# Periph.net
KiCad netlist of a schematic drawn in Altium Designer
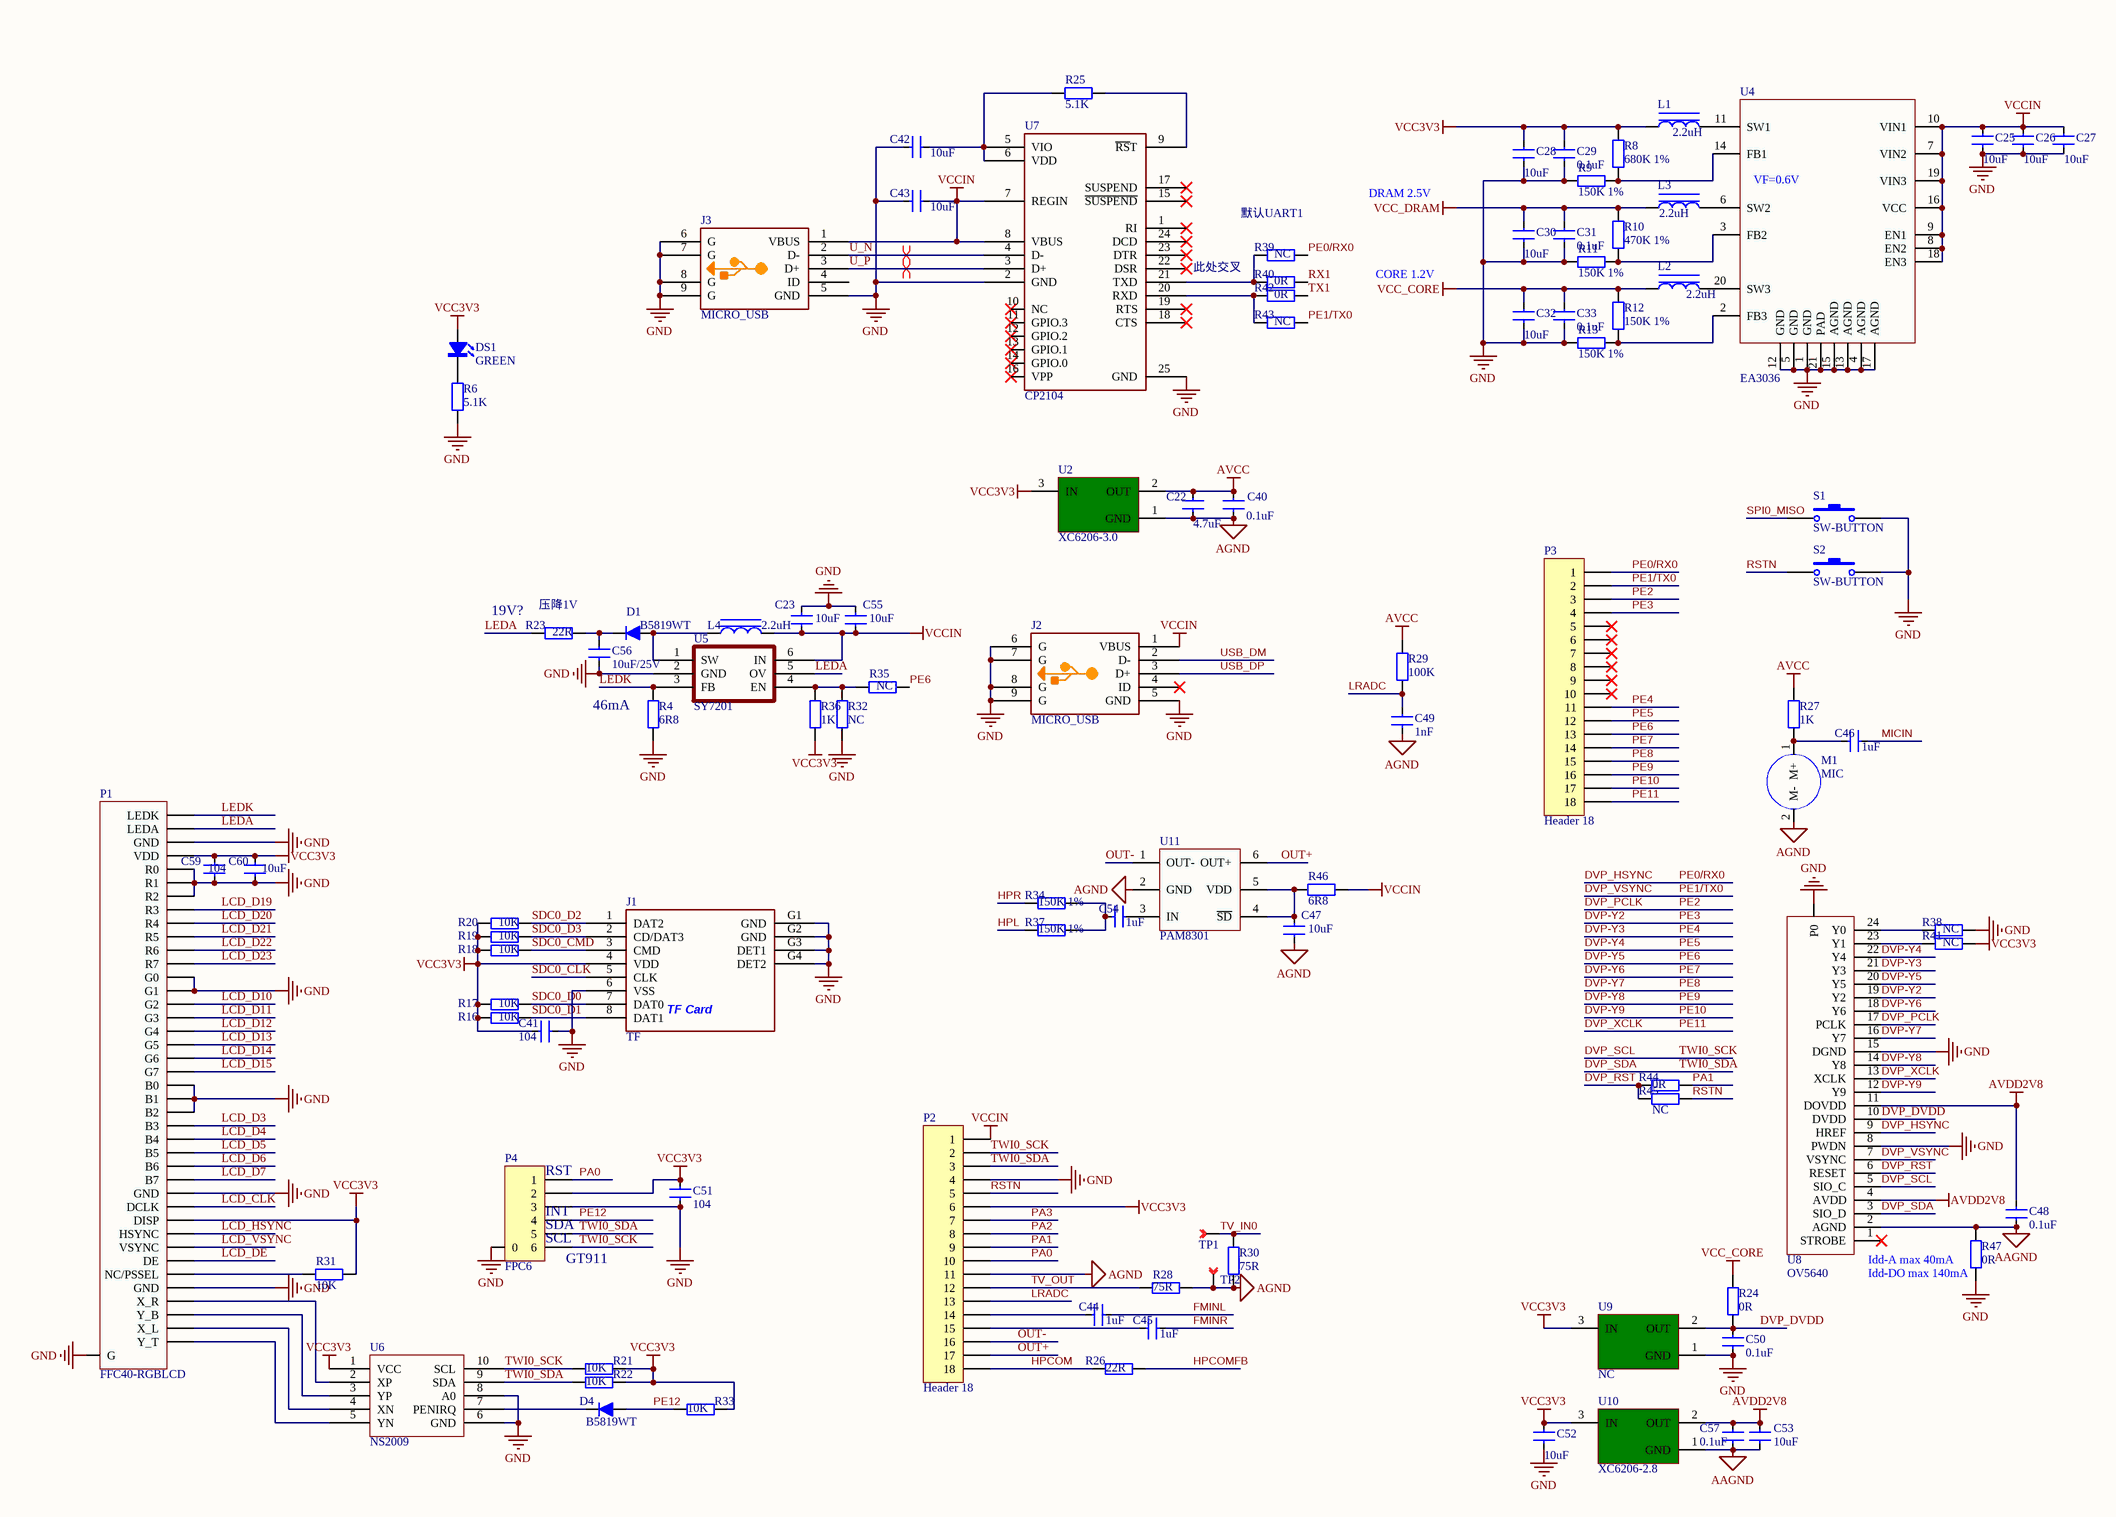
[diagram p0: Periph.SchDoc]

(export (version "E")
  (design (tool "Eeschema 10.0.6"))
  (components
    (comp (ref "C22")
      (value "4.7uF")
      (footprint "C0402")
      (description "普通小电容")
      (libsource (lib "LIB_MANGO") (part "CAP"))
    )
    (comp (ref "C23")
      (value "10uF")
      (footprint "C0402")
      (description "普通小电容")
      (libsource (lib "LIB_MANGO") (part "CAP"))
    )
    (comp (ref "C25")
      (value "10uF")
      (footprint "C0402")
      (description "普通小电容")
      (libsource (lib "LIB_MANGO") (part "CAP"))
    )
    (comp (ref "C26")
      (value "10uF")
      (footprint "C0402")
      (description "普通小电容")
      (libsource (lib "LIB_MANGO") (part "CAP"))
    )
    (comp (ref "C27")
      (value "10uF")
      (footprint "C0402")
      (description "普通小电容")
      (libsource (lib "LIB_MANGO") (part "CAP"))
    )
    (comp (ref "C28")
      (value "10uF")
      (footprint "C0402")
      (description "普通小电容")
      (libsource (lib "LIB_MANGO") (part "CAP"))
    )
    (comp (ref "C29")
      (value "0.1uF")
      (footprint "C0402")
      (description "普通小电容")
      (libsource (lib "LIB_MANGO") (part "CAP"))
    )
    (comp (ref "C30")
      (value "10uF")
      (footprint "C0402")
      (description "普通小电容")
      (libsource (lib "LIB_MANGO") (part "CAP"))
    )
    (comp (ref "C31")
      (value "0.1uF")
      (footprint "C0402")
      (description "普通小电容")
      (libsource (lib "LIB_MANGO") (part "CAP"))
    )
    (comp (ref "C32")
      (value "10uF")
      (footprint "C0402")
      (description "普通小电容")
      (libsource (lib "LIB_MANGO") (part "CAP"))
    )
    (comp (ref "C33")
      (value "0.1uF")
      (footprint "C0402")
      (description "普通小电容")
      (libsource (lib "LIB_MANGO") (part "CAP"))
    )
    (comp (ref "C40")
      (value "0.1uF")
      (footprint "C0402")
      (description "普通小电容")
      (libsource (lib "LIB_MANGO") (part "CAP"))
    )
    (comp (ref "C41")
      (value "104")
      (footprint "C0402")
      (description "普通小电容")
      (libsource (lib "LIB_MANGO") (part "CAP"))
    )
    (comp (ref "C42")
      (value "10uF")
      (footprint "C0402")
      (description "普通小电容")
      (libsource (lib "LIB_MANGO") (part "CAP"))
    )
    (comp (ref "C43")
      (value "10uF")
      (footprint "C0402")
      (description "普通小电容")
      (libsource (lib "LIB_MANGO") (part "CAP"))
    )
    (comp (ref "C44")
      (value "1uF")
      (footprint "C0402")
      (description "普通小电容")
      (libsource (lib "LIB_MANGO") (part "CAP"))
    )
    (comp (ref "C45")
      (value "1uF")
      (footprint "C0402")
      (description "普通小电容")
      (libsource (lib "LIB_MANGO") (part "CAP"))
    )
    (comp (ref "C46")
      (value "1uF")
      (footprint "C0402")
      (description "普通小电容")
      (libsource (lib "LIB_MANGO") (part "CAP"))
    )
    (comp (ref "C47")
      (value "10uF")
      (footprint "C0402")
      (description "普通小电容")
      (libsource (lib "LIB_MANGO") (part "CAP"))
    )
    (comp (ref "C48")
      (value "0.1uF")
      (footprint "C0402")
      (description "普通小电容")
      (libsource (lib "LIB_MANGO") (part "CAP"))
    )
    (comp (ref "C49")
      (value "1nF")
      (footprint "C0402")
      (description "普通小电容")
      (libsource (lib "LIB_MANGO") (part "CAP"))
    )
    (comp (ref "C50")
      (value "0.1uF")
      (footprint "C0402")
      (description "普通小电容")
      (libsource (lib "LIB_MANGO") (part "CAP"))
    )
    (comp (ref "C51")
      (value "104")
      (footprint "C0402")
      (description "普通小电容")
      (libsource (lib "LIB_MANGO") (part "CAP"))
    )
    (comp (ref "C52")
      (value "10uF")
      (footprint "C0402")
      (description "普通小电容")
      (libsource (lib "LIB_MANGO") (part "CAP"))
    )
    (comp (ref "C53")
      (value "10uF")
      (footprint "C0402")
      (description "普通小电容")
      (libsource (lib "LIB_MANGO") (part "CAP"))
    )
    (comp (ref "C54")
      (value "1uF")
      (footprint "C0402")
      (description "普通小电容")
      (libsource (lib "LIB_MANGO") (part "CAP"))
    )
    (comp (ref "C55")
      (value "10uF")
      (footprint "C0402")
      (description "普通小电容")
      (libsource (lib "LIB_MANGO") (part "CAP"))
    )
    (comp (ref "C56")
      (value "10uF/25V")
      (footprint "C0603")
      (description "普通小电容")
      (libsource (lib "LIB_MANGO") (part "CAP"))
    )
    (comp (ref "C57")
      (value "0.1uF")
      (footprint "C0402")
      (description "普通小电容")
      (libsource (lib "LIB_MANGO") (part "CAP"))
    )
    (comp (ref "C59")
      (value "104")
      (footprint "C0402")
      (description "普通小电容")
      (libsource (lib "LIB_MANGO") (part "CAP"))
    )
    (comp (ref "C60")
      (value "10uF")
      (footprint "C0402")
      (description "普通小电容")
      (libsource (lib "LIB_MANGO") (part "CAP"))
    )
    (comp (ref "D1")
      (value "B5819WT")
      (footprint "SOD523")
      (description "普通二极管")
      (libsource (lib "A") (part "Diode"))
    )
    (comp (ref "D4")
      (value "B5819WT")
      (footprint "SOD523")
      (description "普通二极管")
      (libsource (lib "A") (part "Diode"))
    )
    (comp (ref "DS1") (value "GREEN") (footprint "LED0402") (libsource (lib "A") (part "LED")))
    (comp (ref "J1")
      (value "TF")
      (footprint "TFCARD473092651")
      (libsource (lib "LIB_MANGO") (part "TF_473092651"))
    )
    (comp (ref "J2")
      (value "MICRO_USB")
      (footprint "MICROUSB-youxin")
      (libsource (lib "A") (part "MICRO_USB"))
    )
    (comp (ref "J3")
      (value "MICRO_USB")
      (footprint "MICROUSB-youxin")
      (libsource (lib "A") (part "MICRO_USB"))
    )
    (comp (ref "L1")
      (value "2.2uH")
      (footprint "VLS2016")
      (description "普通电感")
      (libsource (lib "LIB_MANGO") (part "L"))
    )
    (comp (ref "L2")
      (value "2.2uH")
      (footprint "VLS2016")
      (description "普通电感")
      (libsource (lib "LIB_MANGO") (part "L"))
    )
    (comp (ref "L3")
      (value "2.2uH")
      (footprint "VLS2016")
      (description "普通电感")
      (libsource (lib "A") (part "L"))
    )
    (comp (ref "L4")
      (value "2.2uH")
      (footprint "VLS3012E")
      (description "普通电感")
      (libsource (lib "LIB_MANGO") (part "L"))
    )
    (comp (ref "M1") (value "MIC") (footprint "MIC") (libsource (lib "LIB_MANGO") (part "MIC")))
    (comp (ref "P1")
      (value "FFC40-RGBLCD")
      (footprint "FFC/SM0.5-1H40")
      (fields (field (name "PUBLISHER") "Altium Limited"))
      (libsource (lib "LIB_MANGO") (part "FFC40-RGBLCD"))
    )
    (comp (ref "P2")
      (value "Header 18")
      (footprint "HDR1X18-M2")
      (description "Header, 18-Pin")
      (fields (field (name "PUBLISHER") "Altium Limited"))
      (libsource (lib "LIB_MANGO") (part "Header 18"))
    )
    (comp (ref "P3")
      (value "Header 18")
      (footprint "HDR1X18-M2")
      (description "Header, 18-Pin")
      (fields (field (name "PUBLISHER") "Altium Limited"))
      (libsource (lib "LIB_MANGO") (part "Header 18"))
    )
    (comp (ref "P4")
      (value "FPC6")
      (footprint "FPC6")
      (fields (field (name "PUBLISHER") "Altium Limited"))
      (libsource (lib "LIB_MANGO") (part "FPC6"))
    )
    (comp (ref "R4")
      (value "6R8")
      (footprint "R0402")
      (description "普通电阻")
      (libsource (lib "LIB_MANGO") (part "RES"))
    )
    (comp (ref "R6")
      (value "5.1K")
      (footprint "R0402")
      (description "普通电阻1%精度")
      (libsource (lib "") (part "RES_2"))
    )
    (comp (ref "R8")
      (value "680K 1%")
      (footprint "R0402")
      (description "普通电阻")
      (libsource (lib "") (part "RES_2"))
    )
    (comp (ref "R9")
      (value "150K 1%")
      (footprint "R0402")
      (description "普通电阻")
      (libsource (lib "") (part "RES_3"))
    )
    (comp (ref "R10")
      (value "470K 1%")
      (footprint "R0402")
      (description "普通电阻")
      (libsource (lib "") (part "RES_2"))
    )
    (comp (ref "R11")
      (value "150K 1%")
      (footprint "R0402")
      (description "普通电阻")
      (libsource (lib "") (part "RES_3"))
    )
    (comp (ref "R12")
      (value "150K 1%")
      (footprint "R0402")
      (description "普通电阻")
      (libsource (lib "") (part "RES_2"))
    )
    (comp (ref "R13")
      (value "150K 1%")
      (footprint "R0402")
      (description "普通电阻")
      (libsource (lib "") (part "RES_3"))
    )
    (comp (ref "R16")
      (value "10K")
      (footprint "R0402")
      (description "普通电阻")
      (libsource (lib "LIB_MANGO") (part "RES"))
    )
    (comp (ref "R17")
      (value "10K")
      (footprint "R0402")
      (description "普通电阻")
      (libsource (lib "LIB_MANGO") (part "RES"))
    )
    (comp (ref "R18")
      (value "10K")
      (footprint "R0402")
      (description "普通电阻")
      (libsource (lib "LIB_MANGO") (part "RES"))
    )
    (comp (ref "R19")
      (value "10K")
      (footprint "R0402")
      (description "普通电阻")
      (libsource (lib "LIB_MANGO") (part "RES"))
    )
    (comp (ref "R20")
      (value "10K")
      (footprint "R0402")
      (description "普通电阻")
      (libsource (lib "LIB_MANGO") (part "RES"))
    )
    (comp (ref "R21")
      (value "10K")
      (footprint "R0402")
      (description "普通电阻")
      (libsource (lib "") (part "RES_1"))
    )
    (comp (ref "R22")
      (value "10K")
      (footprint "R0402")
      (description "普通电阻")
      (libsource (lib "") (part "RES_1"))
    )
    (comp (ref "R23")
      (value "22R")
      (footprint "R0603")
      (description "普通电阻")
      (libsource (lib "") (part "RES_3"))
    )
    (comp (ref "R24")
      (value "0R")
      (footprint "R0402")
      (description "普通电阻")
      (libsource (lib "LIB_MANGO") (part "RES"))
    )
    (comp (ref "R25")
      (value "5.1K")
      (footprint "R0402")
      (description "普通电阻")
      (libsource (lib "") (part "RES_1"))
    )
    (comp (ref "R26")
      (value "22R")
      (footprint "R0402")
      (description "普通电阻")
      (libsource (lib "") (part "RES_1"))
    )
    (comp (ref "R27")
      (value "1K")
      (footprint "R0402")
      (description "普通电阻")
      (libsource (lib "") (part "RES_2"))
    )
    (comp (ref "R28")
      (value "75R")
      (footprint "R0402")
      (description "普通电阻")
      (libsource (lib "") (part "RES_1"))
    )
    (comp (ref "R29")
      (value "100K")
      (footprint "R0402")
      (description "普通电阻")
      (libsource (lib "LIB_MANGO") (part "RES"))
    )
    (comp (ref "R30")
      (value "75R")
      (footprint "R0402")
      (description "普通电阻")
      (libsource (lib "") (part "RES_2"))
    )
    (comp (ref "R31")
      (value "10K")
      (footprint "R0402")
      (description "普通电阻")
      (libsource (lib "") (part "RES_3"))
    )
    (comp (ref "R32")
      (value "NC")
      (footprint "R0402")
      (description "普通电阻")
      (libsource (lib "") (part "RES_2"))
    )
    (comp (ref "R33")
      (value "10K")
      (footprint "R0402")
      (description "普通电阻")
      (libsource (lib "") (part "RES_1"))
    )
    (comp (ref "R34")
      (value "150K 1%")
      (footprint "R0402")
      (description "普通电阻")
      (libsource (lib "") (part "RES_3"))
    )
    (comp (ref "R35")
      (value "NC")
      (footprint "R0402")
      (description "普通电阻")
      (libsource (lib "") (part "RES_1"))
    )
    (comp (ref "R36")
      (value "1K")
      (footprint "R0402")
      (description "普通电阻")
      (libsource (lib "LIB_MANGO") (part "RES"))
    )
    (comp (ref "R37")
      (value "150K 1%")
      (footprint "R0402")
      (description "普通电阻")
      (libsource (lib "") (part "RES_3"))
    )
    (comp (ref "R38")
      (value "NC")
      (footprint "R0402")
      (description "普通电阻")
      (libsource (lib "") (part "RES_1"))
    )
    (comp (ref "R39")
      (value "NC")
      (footprint "R0402")
      (description "普通电阻")
      (libsource (lib "") (part "RES_3"))
    )
    (comp (ref "R40")
      (value "0R")
      (footprint "R0402")
      (description "普通电阻")
      (libsource (lib "") (part "RES_3"))
    )
    (comp (ref "R41")
      (value "NC")
      (footprint "R0402")
      (description "普通电阻")
      (libsource (lib "") (part "RES_1"))
    )
    (comp (ref "R42")
      (value "0R")
      (footprint "R0402")
      (description "普通电阻")
      (libsource (lib "") (part "RES_3"))
    )
    (comp (ref "R43")
      (value "NC")
      (footprint "R0402")
      (description "普通电阻")
      (libsource (lib "") (part "RES_3"))
    )
    (comp (ref "R44")
      (value "0R")
      (footprint "R0402")
      (description "普通电阻")
      (libsource (lib "") (part "RES_3"))
    )
    (comp (ref "R45")
      (value "NC")
      (footprint "R0402")
      (description "普通电阻")
      (libsource (lib "") (part "RES_1"))
    )
    (comp (ref "R46")
      (value "6R8")
      (footprint "R0402")
      (description "普通电阻")
      (libsource (lib "") (part "RES_3"))
    )
    (comp (ref "R47")
      (value "0R")
      (footprint "R0402")
      (description "普通电阻")
      (libsource (lib "") (part "RES_2"))
    )
    (comp (ref "S1")
      (value "SW-BUTTON")
      (footprint "MINIBUTTON")
      (libsource (lib "LIB_MANGO") (part "SW-BUTTON"))
    )
    (comp (ref "S2")
      (value "SW-BUTTON")
      (footprint "MINIBUTTON")
      (libsource (lib "LIB_MANGO") (part "SW-BUTTON"))
    )
    (comp (ref "TP1")
      (value "TEST POINT")
      (footprint "TEST-POINT")
      (description "Description")
      (libsource (lib "LIB_MANGO") (part "TP"))
    )
    (comp (ref "TP2")
      (value "TEST POINT")
      (footprint "TEST-POINT")
      (description "Description")
      (libsource (lib "LIB_MANGO") (part "TP"))
    )
    (comp (ref "U2") (value "XC6206-3.0") (footprint "SOT23") (libsource (lib "LIB_MANGO") (part "XC6206")))
    (comp (ref "U4")
      (value "EA3036")
      (footprint "QFN40P300X300X80_HS-21N")
      (libsource (lib "LIB_MANGO") (part "EA3036"))
    )
    (comp (ref "U5") (value "SY7201") (footprint "SOT23-6") (libsource (lib "LIB_MANGO") (part "PT4101")))
    (comp (ref "U6") (value "NS2009") (footprint "TSSOP10") (libsource (lib "LIB_MANGO") (part "NS2009")))
    (comp (ref "U7") (value "CP2104") (footprint "QFN24") (libsource (lib "LIB_MANGO") (part "CP2104")))
    (comp (ref "U8")
      (value "OV5640")
      (footprint "FFC/SM0.5-1H24 - OV2640")
      (description "Header, 24-Pin")
      (fields (field (name "PUBLISHER") "Altium Limited"))
      (libsource (lib "A") (part "OV5640"))
    )
    (comp (ref "U9") (value "NC") (footprint "SOT23") (libsource (lib "LIB_MANGO") (part "XC6206")))
    (comp (ref "U10") (value "XC6206-2.8") (footprint "SOT23") (libsource (lib "LIB_MANGO") (part "XC6206")))
    (comp (ref "U11") (value "PAM8301") (footprint "SOT23-6") (libsource (lib "LIB_MANGO") (part "PAM8301")))
  )
  (nets
    (net (code "1") (name "/DVP-Y2") (class "Default")
      (node (ref "P3") (pin "4") (pinfunction "4_4") (pintype "passive"))
      (node (ref "U8") (pin "19") (pinfunction "Y2_19") (pintype "passive"))
    )
    (net (code "2") (name "/DVP-Y3") (class "Default")
      (node (ref "P3") (pin "11") (pinfunction "11_11") (pintype "passive"))
      (node (ref "U8") (pin "21") (pinfunction "Y3_21") (pintype "passive"))
    )
    (net (code "3") (name "/DVP-Y4") (class "Default")
      (node (ref "P3") (pin "12") (pinfunction "12_12") (pintype "passive"))
      (node (ref "U8") (pin "22") (pinfunction "Y4_22") (pintype "passive"))
    )
    (net (code "4") (name "/DVP-Y5") (class "Default")
      (node (ref "P3") (pin "13") (pinfunction "13_13") (pintype "passive"))
      (node (ref "R35") (pin "2") (pinfunction "2_2") (pintype "passive"))
      (node (ref "U8") (pin "20") (pinfunction "Y5_20") (pintype "passive"))
    )
    (net (code "5") (name "/DVP-Y6") (class "Default")
      (node (ref "P3") (pin "14") (pinfunction "14_14") (pintype "passive"))
      (node (ref "U8") (pin "18") (pinfunction "Y6_18") (pintype "passive"))
    )
    (net (code "6") (name "/DVP-Y7") (class "Default")
      (node (ref "P3") (pin "15") (pinfunction "15_15") (pintype "passive"))
      (node (ref "U8") (pin "16") (pinfunction "Y7_16") (pintype "passive"))
    )
    (net (code "7") (name "/DVP-Y8") (class "Default")
      (node (ref "P3") (pin "16") (pinfunction "16_16") (pintype "passive"))
      (node (ref "U8") (pin "14") (pinfunction "Y8_14") (pintype "passive"))
    )
    (net (code "8") (name "/DVP-Y9") (class "Default")
      (node (ref "P3") (pin "17") (pinfunction "17_17") (pintype "passive"))
      (node (ref "U8") (pin "12") (pinfunction "Y9_12") (pintype "passive"))
    )
    (net (code "9") (name "/DVP_DVDD") (class "Default")
      (node (ref "C50") (pin "2") (pinfunction "2_2") (pintype "passive"))
      (node (ref "R24") (pin "1") (pinfunction "1_1") (pintype "passive"))
      (node (ref "U8") (pin "10") (pinfunction "DVDD_10") (pintype "passive"))
      (node (ref "U9") (pin "2") (pinfunction "OUT_2") (pintype "passive"))
    )
    (net (code "10") (name "/DVP_HSYNC") (class "Default")
      (node (ref "P3") (pin "1") (pinfunction "1_1") (pintype "passive"))
      (node (ref "R39") (pin "1") (pinfunction "1_1") (pintype "passive"))
      (node (ref "U8") (pin "9") (pinfunction "HREF_9") (pintype "passive"))
    )
    (net (code "11") (name "/DVP_PCLK") (class "Default")
      (node (ref "P3") (pin "3") (pinfunction "3_3") (pintype "passive"))
      (node (ref "U8") (pin "17") (pinfunction "PCLK_17") (pintype "passive"))
    )
    (net (code "12") (name "/DVP_RST") (class "Default")
      (node (ref "R44") (pin "2") (pinfunction "2_2") (pintype "passive"))
      (node (ref "R45") (pin "1") (pinfunction "1_1") (pintype "passive"))
      (node (ref "U8") (pin "6") (pinfunction "RESET_6") (pintype "passive"))
    )
    (net (code "13") (name "/DVP_SCL") (class "Default")
      (node (ref "P2") (pin "2") (pinfunction "2_2") (pintype "passive"))
      (node (ref "P4") (pin "6") (pinfunction "6_6") (pintype "passive"))
      (node (ref "R21") (pin "1") (pinfunction "1_1") (pintype "passive"))
      (node (ref "U6") (pin "10") (pinfunction "SCL_10") (pintype "passive"))
      (node (ref "U8") (pin "5") (pinfunction "SIO_C_5") (pintype "passive"))
    )
    (net (code "14") (name "/DVP_SDA") (class "Default")
      (node (ref "P2") (pin "3") (pinfunction "3_3") (pintype "passive"))
      (node (ref "P4") (pin "5") (pinfunction "5_5") (pintype "passive"))
      (node (ref "R22") (pin "1") (pinfunction "1_1") (pintype "passive"))
      (node (ref "U6") (pin "9") (pinfunction "SDA_9") (pintype "passive"))
      (node (ref "U8") (pin "3") (pinfunction "SIO_D_3") (pintype "passive"))
    )
    (net (code "15") (name "/DVP_VSYNC") (class "Default")
      (node (ref "P3") (pin "2") (pinfunction "2_2") (pintype "passive"))
      (node (ref "R43") (pin "1") (pinfunction "1_1") (pintype "passive"))
      (node (ref "U8") (pin "7") (pinfunction "VSYNC_7") (pintype "passive"))
    )
    (net (code "16") (name "/DVP_XCLK") (class "Default")
      (node (ref "P3") (pin "18") (pinfunction "18_18") (pintype "passive"))
      (node (ref "U8") (pin "13") (pinfunction "XCLK_13") (pintype "passive"))
    )
    (net (code "17") (name "/FMINL") (class "Default")
      (node (ref "C44") (pin "2") (pinfunction "2_2") (pintype "passive"))
    )
    (net (code "18") (name "/FMINR") (class "Default")
      (node (ref "C45") (pin "2") (pinfunction "2_2") (pintype "passive"))
    )
    (net (code "19") (name "/HPCOM") (class "Default")
      (node (ref "P2") (pin "18") (pinfunction "18_18") (pintype "passive"))
      (node (ref "R26") (pin "1") (pinfunction "1_1") (pintype "passive"))
    )
    (net (code "20") (name "/HPCOMFB") (class "Default")
      (node (ref "R26") (pin "2") (pinfunction "2_2") (pintype "passive"))
    )
    (net (code "21") (name "/HPL") (class "Default")
      (node (ref "R37") (pin "2") (pinfunction "2_2") (pintype "passive"))
    )
    (net (code "22") (name "/HPR") (class "Default")
      (node (ref "R34") (pin "2") (pinfunction "2_2") (pintype "passive"))
    )
    (net (code "23") (name "/LCD_CLK") (class "Default")
      (node (ref "P1") (pin "30") (pinfunction "DCLK_30") (pintype "passive"))
    )
    (net (code "24") (name "/LCD_D3") (class "Default")
      (node (ref "P1") (pin "24") (pinfunction "B3_24") (pintype "passive"))
    )
    (net (code "25") (name "/LCD_D4") (class "Default")
      (node (ref "P1") (pin "25") (pinfunction "B4_25") (pintype "passive"))
    )
    (net (code "26") (name "/LCD_D5") (class "Default")
      (node (ref "P1") (pin "26") (pinfunction "B5_26") (pintype "passive"))
    )
    (net (code "27") (name "/LCD_D6") (class "Default")
      (node (ref "P1") (pin "27") (pinfunction "B6_27") (pintype "passive"))
    )
    (net (code "28") (name "/LCD_D7") (class "Default")
      (node (ref "P1") (pin "28") (pinfunction "B7_28") (pintype "passive"))
    )
    (net (code "29") (name "/LCD_D10") (class "Default")
      (node (ref "P1") (pin "15") (pinfunction "G2_15") (pintype "passive"))
    )
    (net (code "30") (name "/LCD_D11") (class "Default")
      (node (ref "P1") (pin "16") (pinfunction "G3_16") (pintype "passive"))
    )
    (net (code "31") (name "/LCD_D12") (class "Default")
      (node (ref "P1") (pin "17") (pinfunction "G4_17") (pintype "passive"))
    )
    (net (code "32") (name "/LCD_D13") (class "Default")
      (node (ref "P1") (pin "18") (pinfunction "G5_18") (pintype "passive"))
    )
    (net (code "33") (name "/LCD_D14") (class "Default")
      (node (ref "P1") (pin "19") (pinfunction "G6_19") (pintype "passive"))
    )
    (net (code "34") (name "/LCD_D15") (class "Default")
      (node (ref "P1") (pin "20") (pinfunction "G7_20") (pintype "passive"))
    )
    (net (code "35") (name "/LCD_D19") (class "Default")
      (node (ref "P1") (pin "8") (pinfunction "R3_8") (pintype "passive"))
    )
    (net (code "36") (name "/LCD_D20") (class "Default")
      (node (ref "P1") (pin "9") (pinfunction "R4_9") (pintype "passive"))
    )
    (net (code "37") (name "/LCD_D21") (class "Default")
      (node (ref "P1") (pin "10") (pinfunction "R5_10") (pintype "passive"))
    )
    (net (code "38") (name "/LCD_D22") (class "Default")
      (node (ref "P1") (pin "11") (pinfunction "R6_11") (pintype "passive"))
    )
    (net (code "39") (name "/LCD_D23") (class "Default")
      (node (ref "P1") (pin "12") (pinfunction "R7_12") (pintype "passive"))
    )
    (net (code "40") (name "/LCD_DE") (class "Default")
      (node (ref "P1") (pin "34") (pinfunction "DE_34") (pintype "passive"))
    )
    (net (code "41") (name "/LCD_HSYNC") (class "Default")
      (node (ref "P1") (pin "32") (pinfunction "HSYNC_32") (pintype "passive"))
    )
    (net (code "42") (name "/LCD_VSYNC") (class "Default")
      (node (ref "P1") (pin "33") (pinfunction "VSYNC_33") (pintype "passive"))
    )
    (net (code "43") (name "/LEDA") (class "Default")
      (node (ref "P1") (pin "2") (pinfunction "LEDA_2") (pintype "passive"))
      (node (ref "R23") (pin "2") (pinfunction "2_2") (pintype "passive"))
      (node (ref "U5") (pin "5") (pinfunction "OV_5") (pintype "passive"))
    )
    (net (code "44") (name "/LEDK") (class "Default")
      (node (ref "P1") (pin "1") (pinfunction "LEDK_1") (pintype "passive"))
      (node (ref "R4") (pin "2") (pinfunction "2_2") (pintype "passive"))
      (node (ref "U5") (pin "3") (pinfunction "FB_3") (pintype "passive"))
    )
    (net (code "45") (name "/LRADC") (class "Default")
      (node (ref "C49") (pin "2") (pinfunction "2_2") (pintype "passive"))
      (node (ref "P2") (pin "13") (pinfunction "13_13") (pintype "passive"))
      (node (ref "R29") (pin "1") (pinfunction "1_1") (pintype "passive"))
    )
    (net (code "46") (name "/MICIN") (class "Default")
      (node (ref "C46") (pin "2") (pinfunction "2_2") (pintype "passive"))
    )
    (net (code "47") (name "/OUT+") (class "Default")
      (node (ref "P2") (pin "17") (pinfunction "17_17") (pintype "passive"))
      (node (ref "U11") (pin "6") (pinfunction "OUT+_6") (pintype "passive"))
    )
    (net (code "48") (name "/OUT-") (class "Default")
      (node (ref "P2") (pin "16") (pinfunction "16_16") (pintype "passive"))
      (node (ref "U11") (pin "1") (pinfunction "OUT-_1") (pintype "passive"))
    )
    (net (code "49") (name "/PA0") (class "Default")
      (node (ref "P2") (pin "10") (pinfunction "10_10") (pintype "passive"))
      (node (ref "P4") (pin "1") (pinfunction "1_1") (pintype "passive"))
    )
    (net (code "50") (name "/PA1") (class "Default")
      (node (ref "P2") (pin "9") (pinfunction "9_9") (pintype "passive"))
      (node (ref "R44") (pin "1") (pinfunction "1_1") (pintype "passive"))
    )
    (net (code "51") (name "/PA2") (class "Default")
      (node (ref "P2") (pin "8") (pinfunction "8_8") (pintype "passive"))
    )
    (net (code "52") (name "/PA3") (class "Default")
      (node (ref "P2") (pin "7") (pinfunction "7_7") (pintype "passive"))
    )
    (net (code "53") (name "/PE12") (class "Default")
      (node (ref "D4") (pin "A") (pinfunction "A_A") (pintype "passive"))
      (node (ref "P4") (pin "4") (pinfunction "4_4") (pintype "passive"))
      (node (ref "R33") (pin "1") (pinfunction "1_1") (pintype "passive"))
    )
    (net (code "54") (name "/RSTN") (class "Default")
      (node (ref "P2") (pin "5") (pinfunction "5_5") (pintype "passive"))
      (node (ref "R45") (pin "2") (pinfunction "2_2") (pintype "passive"))
      (node (ref "S2") (pin "1") (pinfunction "1_1") (pintype "passive"))
    )
    (net (code "55") (name "/RX1") (class "Default")
      (node (ref "R40") (pin "1") (pinfunction "1_1") (pintype "passive"))
    )
    (net (code "56") (name "/SDC0_CLK") (class "Default")
      (node (ref "J1") (pin "5") (pinfunction "CLK_5") (pintype "passive"))
    )
    (net (code "57") (name "/SDC0_CMD") (class "Default")
      (node (ref "J1") (pin "3") (pinfunction "CMD_3") (pintype "passive"))
      (node (ref "R18") (pin "2") (pinfunction "2_2") (pintype "passive"))
    )
    (net (code "58") (name "/SDC0_D0") (class "Default")
      (node (ref "J1") (pin "7") (pinfunction "DAT0_7") (pintype "passive"))
      (node (ref "R17") (pin "2") (pinfunction "2_2") (pintype "passive"))
    )
    (net (code "59") (name "/SDC0_D1") (class "Default")
      (node (ref "J1") (pin "8") (pinfunction "DAT1_8") (pintype "passive"))
      (node (ref "R16") (pin "2") (pinfunction "2_2") (pintype "passive"))
    )
    (net (code "60") (name "/SDC0_D2") (class "Default")
      (node (ref "J1") (pin "1") (pinfunction "DAT2_1") (pintype "passive"))
      (node (ref "R20") (pin "2") (pinfunction "2_2") (pintype "passive"))
    )
    (net (code "61") (name "/SDC0_D3") (class "Default")
      (node (ref "J1") (pin "2") (pinfunction "CD/DAT3_2") (pintype "passive"))
      (node (ref "R19") (pin "2") (pinfunction "2_2") (pintype "passive"))
    )
    (net (code "62") (name "/SPI0_MISO") (class "Default")
      (node (ref "S1") (pin "1") (pinfunction "1_1") (pintype "passive"))
    )
    (net (code "63") (name "/TV_IN0") (class "Default")
      (node (ref "R30") (pin "1") (pinfunction "1_1") (pintype "passive"))
      (node (ref "TP1") (pin "1") (pinfunction "1_1") (pintype "passive"))
    )
    (net (code "64") (name "/TV_OUT") (class "Default")
      (node (ref "P2") (pin "12") (pinfunction "12_12") (pintype "passive"))
      (node (ref "R28") (pin "1") (pinfunction "1_1") (pintype "passive"))
    )
    (net (code "65") (name "/TX1") (class "Default")
      (node (ref "R42") (pin "1") (pinfunction "1_1") (pintype "passive"))
    )
    (net (code "66") (name "/USB_DM") (class "Default")
      (node (ref "J2") (pin "2") (pinfunction "D-_2") (pintype "passive"))
    )
    (net (code "67") (name "/USB_DP") (class "Default")
      (node (ref "J2") (pin "3") (pinfunction "D+_3") (pintype "passive"))
    )
    (net (code "68") (name "/U_N") (class "Default")
      (node (ref "J3") (pin "2") (pinfunction "D-_2") (pintype "passive"))
      (node (ref "U7") (pin "4") (pinfunction "D-_4") (pintype "passive"))
    )
    (net (code "69") (name "/U_P") (class "Default")
      (node (ref "J3") (pin "3") (pinfunction "D+_3") (pintype "passive"))
      (node (ref "U7") (pin "3") (pinfunction "D+_3") (pintype "passive"))
    )
    (net (code "70") (name "AAGND") (class "Default")
      (node (ref "C48") (pin "1") (pinfunction "1_1") (pintype "passive"))
      (node (ref "C53") (pin "2") (pinfunction "2_2") (pintype "passive"))
      (node (ref "C57") (pin "1") (pinfunction "1_1") (pintype "passive"))
      (node (ref "R47") (pin "1") (pinfunction "1_1") (pintype "passive"))
      (node (ref "U10") (pin "1") (pinfunction "GND_1") (pintype "passive"))
      (node (ref "U8") (pin "2") (pinfunction "AGND_2") (pintype "passive"))
    )
    (net (code "71") (name "AGND") (class "Default")
      (node (ref "C22") (pin "1") (pinfunction "1_1") (pintype "passive"))
      (node (ref "C40") (pin "1") (pinfunction "1_1") (pintype "passive"))
      (node (ref "C47") (pin "2") (pinfunction "2_2") (pintype "passive"))
      (node (ref "C49") (pin "1") (pinfunction "1_1") (pintype "passive"))
      (node (ref "M1") (pin "2") (pinfunction "M-_2") (pintype "passive"))
      (node (ref "P2") (pin "11") (pinfunction "11_11") (pintype "passive"))
      (node (ref "R28") (pin "2") (pinfunction "2_2") (pintype "passive"))
      (node (ref "R30") (pin "2") (pinfunction "2_2") (pintype "passive"))
      (node (ref "TP2") (pin "1") (pinfunction "1_1") (pintype "passive"))
      (node (ref "U11") (pin "2") (pinfunction "GND_2") (pintype "passive"))
      (node (ref "U2") (pin "1") (pinfunction "GND_1") (pintype "passive"))
    )
    (net (code "72") (name "AVCC") (class "Default")
      (node (ref "C22") (pin "2") (pinfunction "2_2") (pintype "passive"))
      (node (ref "C40") (pin "2") (pinfunction "2_2") (pintype "passive"))
      (node (ref "R27") (pin "1") (pinfunction "1_1") (pintype "passive"))
      (node (ref "R29") (pin "2") (pinfunction "2_2") (pintype "passive"))
      (node (ref "U2") (pin "2") (pinfunction "OUT_2") (pintype "passive"))
    )
    (net (code "73") (name "AVDD2V8") (class "Default")
      (node (ref "C48") (pin "2") (pinfunction "2_2") (pintype "passive"))
      (node (ref "C53") (pin "1") (pinfunction "1_1") (pintype "passive"))
      (node (ref "C57") (pin "2") (pinfunction "2_2") (pintype "passive"))
      (node (ref "U10") (pin "2") (pinfunction "OUT_2") (pintype "passive"))
      (node (ref "U8") (pin "11") (pinfunction "DOVDD_11") (pintype "passive"))
      (node (ref "U8") (pin "4") (pinfunction "AVDD_4") (pintype "passive"))
    )
    (net (code "74") (name "GND") (class "Default")
      (node (ref "C23") (pin "2") (pinfunction "2_2") (pintype "passive"))
      (node (ref "C25") (pin "2") (pinfunction "2_2") (pintype "passive"))
      (node (ref "C26") (pin "2") (pinfunction "2_2") (pintype "passive"))
      (node (ref "C27") (pin "2") (pinfunction "2_2") (pintype "passive"))
      (node (ref "C28") (pin "2") (pinfunction "2_2") (pintype "passive"))
      (node (ref "C29") (pin "1") (pinfunction "1_1") (pintype "passive"))
      (node (ref "C30") (pin "2") (pinfunction "2_2") (pintype "passive"))
      (node (ref "C31") (pin "1") (pinfunction "1_1") (pintype "passive"))
      (node (ref "C32") (pin "2") (pinfunction "2_2") (pintype "passive"))
      (node (ref "C33") (pin "1") (pinfunction "1_1") (pintype "passive"))
      (node (ref "C41") (pin "2") (pinfunction "2_2") (pintype "passive"))
      (node (ref "C42") (pin "2") (pinfunction "2_2") (pintype "passive"))
      (node (ref "C43") (pin "1") (pinfunction "1_1") (pintype "passive"))
      (node (ref "C50") (pin "1") (pinfunction "1_1") (pintype "passive"))
      (node (ref "C51") (pin "1") (pinfunction "1_1") (pintype "passive"))
      (node (ref "C52") (pin "2") (pinfunction "2_2") (pintype "passive"))
      (node (ref "C55") (pin "1") (pinfunction "1_1") (pintype "passive"))
      (node (ref "C56") (pin "1") (pinfunction "1_1") (pintype "passive"))
      (node (ref "C59") (pin "2") (pinfunction "2_2") (pintype "passive"))
      (node (ref "C60") (pin "1") (pinfunction "1_1") (pintype "passive"))
      (node (ref "J1") (pin "6") (pinfunction "VSS_6") (pintype "power_in"))
      (node (ref "J1") (pin "G1") (pinfunction "GND_G1") (pintype "power_in"))
      (node (ref "J1") (pin "G2") (pinfunction "GND_G2") (pintype "power_in"))
      (node (ref "J1") (pin "G3") (pinfunction "DET1_G3") (pintype "power_in"))
      (node (ref "J1") (pin "G4") (pinfunction "DET2_G4") (pintype "power_in"))
      (node (ref "J2") (pin "5") (pinfunction "GND_5") (pintype "power_in"))
      (node (ref "J2") (pin "6") (pinfunction "G_6") (pintype "passive"))
      (node (ref "J2") (pin "7") (pinfunction "G_7") (pintype "passive"))
      (node (ref "J2") (pin "8") (pinfunction "G_8") (pintype "passive"))
      (node (ref "J2") (pin "9") (pinfunction "G_9") (pintype "passive"))
      (node (ref "J3") (pin "5") (pinfunction "GND_5") (pintype "power_in"))
      (node (ref "J3") (pin "6") (pinfunction "G_6") (pintype "passive"))
      (node (ref "J3") (pin "7") (pinfunction "G_7") (pintype "passive"))
      (node (ref "J3") (pin "8") (pinfunction "G_8") (pintype "passive"))
      (node (ref "J3") (pin "9") (pinfunction "G_9") (pintype "passive"))
      (node (ref "P1") (pin "13") (pinfunction "G0_13") (pintype "passive"))
      (node (ref "P1") (pin "14") (pinfunction "G1_14") (pintype "passive"))
      (node (ref "P1") (pin "21") (pinfunction "B0_21") (pintype "passive"))
      (node (ref "P1") (pin "22") (pinfunction "B1_22") (pintype "passive"))
      (node (ref "P1") (pin "23") (pinfunction "B2_23") (pintype "passive"))
      (node (ref "P1") (pin "29") (pinfunction "GND_29") (pintype "passive"))
      (node (ref "P1") (pin "3") (pinfunction "GND_3") (pintype "passive"))
      (node (ref "P1") (pin "36") (pinfunction "GND_36") (pintype "passive"))
      (node (ref "P1") (pin "5") (pinfunction "R0_5") (pintype "passive"))
      (node (ref "P1") (pin "6") (pinfunction "R1_6") (pintype "passive"))
      (node (ref "P1") (pin "7") (pinfunction "R2_7") (pintype "passive"))
      (node (ref "P1") (pin "G") (pinfunction "G_G") (pintype "passive"))
      (node (ref "P2") (pin "4") (pinfunction "4_4") (pintype "passive"))
      (node (ref "P4") (pin "0") (pinfunction "0_0") (pintype "passive"))
      (node (ref "P4") (pin "3") (pinfunction "3_3") (pintype "passive"))
      (node (ref "R11") (pin "2") (pinfunction "2_2") (pintype "passive"))
      (node (ref "R13") (pin "2") (pinfunction "2_2") (pintype "passive"))
      (node (ref "R32") (pin "2") (pinfunction "2_2") (pintype "passive"))
      (node (ref "R38") (pin "2") (pinfunction "2_2") (pintype "passive"))
      (node (ref "R4") (pin "1") (pinfunction "1_1") (pintype "passive"))
      (node (ref "R47") (pin "2") (pinfunction "2_2") (pintype "passive"))
      (node (ref "R6") (pin "2") (pinfunction "2_2") (pintype "passive"))
      (node (ref "R9") (pin "2") (pinfunction "2_2") (pintype "passive"))
      (node (ref "S1") (pin "2") (pinfunction "2_2") (pintype "passive"))
      (node (ref "S2") (pin "2") (pinfunction "2_2") (pintype "passive"))
      (node (ref "U4") (pin "1") (pinfunction "GND_1") (pintype "passive"))
      (node (ref "U4") (pin "12") (pinfunction "GND_12") (pintype "passive"))
      (node (ref "U4") (pin "13") (pinfunction "AGND_13") (pintype "passive"))
      (node (ref "U4") (pin "15") (pinfunction "AGND_15") (pintype "passive"))
      (node (ref "U4") (pin "17") (pinfunction "AGND_17") (pintype "passive"))
      (node (ref "U4") (pin "21") (pinfunction "PAD_21") (pintype "passive"))
      (node (ref "U4") (pin "4") (pinfunction "AGND_4") (pintype "passive"))
      (node (ref "U4") (pin "5") (pinfunction "GND_5") (pintype "passive"))
      (node (ref "U5") (pin "2") (pinfunction "GND_2") (pintype "passive"))
      (node (ref "U6") (pin "6") (pinfunction "GND_6") (pintype "passive"))
      (node (ref "U6") (pin "8") (pinfunction "A0_8") (pintype "passive"))
      (node (ref "U7") (pin "2") (pinfunction "GND_2") (pintype "power_in"))
      (node (ref "U7") (pin "25") (pinfunction "GND_25") (pintype "power_in"))
      (node (ref "U8") (pin "15") (pinfunction "DGND_15") (pintype "passive"))
      (node (ref "U8") (pin "8") (pinfunction "PWDN_8") (pintype "passive"))
      (node (ref "U8") (pin "P0") (pinfunction "P0_P0") (pintype "passive"))
      (node (ref "U9") (pin "1") (pinfunction "GND_1") (pintype "passive"))
    )
    (net (code "75") (name "Net-(C44-Pad1)") (class "Default")
      (node (ref "C44") (pin "1") (pinfunction "1_1") (pintype "passive"))
      (node (ref "P2") (pin "14") (pinfunction "14_14") (pintype "passive"))
    )
    (net (code "76") (name "Net-(C45-Pad1)") (class "Default")
      (node (ref "C45") (pin "1") (pinfunction "1_1") (pintype "passive"))
      (node (ref "P2") (pin "15") (pinfunction "15_15") (pintype "passive"))
    )
    (net (code "77") (name "Net-(C54-Pad1)") (class "Default")
      (node (ref "C54") (pin "1") (pinfunction "1_1") (pintype "passive"))
      (node (ref "R34") (pin "1") (pinfunction "1_1") (pintype "passive"))
      (node (ref "R37") (pin "1") (pinfunction "1_1") (pintype "passive"))
    )
    (net (code "78") (name "Net-(C56-Pad2)") (class "Default")
      (node (ref "C56") (pin "2") (pinfunction "2_2") (pintype "passive"))
      (node (ref "D1") (pin "K") (pinfunction "K_K") (pintype "passive"))
      (node (ref "R23") (pin "1") (pinfunction "1_1") (pintype "passive"))
    )
    (net (code "79") (name "Net-(DS1-2)") (class "Default")
      (node (ref "DS1") (pin "K") (pinfunction "2_K") (pintype "passive"))
      (node (ref "R6") (pin "1") (pinfunction "1_1") (pintype "passive"))
    )
    (net (code "80") (name "Net-(M1-M+)") (class "Default")
      (node (ref "C46") (pin "1") (pinfunction "1_1") (pintype "passive"))
      (node (ref "M1") (pin "1") (pinfunction "M+_1") (pintype "passive"))
      (node (ref "R27") (pin "2") (pinfunction "2_2") (pintype "passive"))
    )
    (net (code "81") (name "Net-(P1-NC{slash}PSSEL)") (class "Default")
      (node (ref "P1") (pin "35") (pinfunction "NC/PSSEL_35") (pintype "passive"))
      (node (ref "R31") (pin "2") (pinfunction "2_2") (pintype "passive"))
    )
    (net (code "82") (name "Net-(P1-X_L)") (class "Default")
      (node (ref "P1") (pin "39") (pinfunction "X_L_39") (pintype "passive"))
      (node (ref "U6") (pin "4") (pinfunction "XN_4") (pintype "passive"))
    )
    (net (code "83") (name "Net-(P1-X_R)") (class "Default")
      (node (ref "P1") (pin "37") (pinfunction "X_R_37") (pintype "passive"))
      (node (ref "U6") (pin "2") (pinfunction "XP_2") (pintype "passive"))
    )
    (net (code "84") (name "Net-(P1-Y_B)") (class "Default")
      (node (ref "P1") (pin "38") (pinfunction "Y_B_38") (pintype "passive"))
      (node (ref "U6") (pin "3") (pinfunction "YP_3") (pintype "passive"))
    )
    (net (code "85") (name "Net-(P1-Y_T)") (class "Default")
      (node (ref "P1") (pin "40") (pinfunction "Y_T_40") (pintype "passive"))
      (node (ref "U6") (pin "5") (pinfunction "YN_5") (pintype "passive"))
    )
    (net (code "86") (name "Net-(U4-FB1)") (class "Default")
      (node (ref "R8") (pin "2") (pinfunction "2_2") (pintype "passive"))
      (node (ref "R9") (pin "1") (pinfunction "1_1") (pintype "passive"))
      (node (ref "U4") (pin "14") (pinfunction "FB1_14") (pintype "passive"))
    )
    (net (code "87") (name "Net-(U4-FB2)") (class "Default")
      (node (ref "R10") (pin "2") (pinfunction "2_2") (pintype "passive"))
      (node (ref "R11") (pin "1") (pinfunction "1_1") (pintype "passive"))
      (node (ref "U4") (pin "3") (pinfunction "FB2_3") (pintype "passive"))
    )
    (net (code "88") (name "Net-(U4-FB3)") (class "Default")
      (node (ref "R12") (pin "2") (pinfunction "2_2") (pintype "passive"))
      (node (ref "R13") (pin "1") (pinfunction "1_1") (pintype "passive"))
      (node (ref "U4") (pin "2") (pinfunction "FB3_2") (pintype "passive"))
    )
    (net (code "89") (name "Net-(U4-SW1)") (class "Default")
      (node (ref "L1") (pin "1") (pinfunction "1_1") (pintype "passive"))
      (node (ref "U4") (pin "11") (pinfunction "SW1_11") (pintype "passive"))
    )
    (net (code "90") (name "Net-(U4-SW2)") (class "Default")
      (node (ref "L3") (pin "1") (pinfunction "1_1") (pintype "passive"))
      (node (ref "U4") (pin "6") (pinfunction "SW2_6") (pintype "passive"))
    )
    (net (code "91") (name "Net-(U4-SW3)") (class "Default")
      (node (ref "L2") (pin "1") (pinfunction "1_1") (pintype "passive"))
      (node (ref "U4") (pin "20") (pinfunction "SW3_20") (pintype "passive"))
    )
    (net (code "92") (name "Net-(U5-EN)") (class "Default")
      (node (ref "R32") (pin "1") (pinfunction "1_1") (pintype "passive"))
      (node (ref "R35") (pin "1") (pinfunction "1_1") (pintype "passive"))
      (node (ref "R36") (pin "2") (pinfunction "2_2") (pintype "passive"))
      (node (ref "U5") (pin "4") (pinfunction "EN_4") (pintype "passive"))
    )
    (net (code "93") (name "Net-(U5-SW)") (class "Default")
      (node (ref "D1") (pin "A") (pinfunction "A_A") (pintype "passive"))
      (node (ref "L4") (pin "2") (pinfunction "2_2") (pintype "passive"))
      (node (ref "U5") (pin "1") (pinfunction "SW_1") (pintype "passive"))
    )
    (net (code "94") (name "Net-(U6-PENIRQ)") (class "Default")
      (node (ref "D4") (pin "K") (pinfunction "K_K") (pintype "passive"))
      (node (ref "U6") (pin "7") (pinfunction "PENIRQ_7") (pintype "passive"))
    )
    (net (code "95") (name "Net-(U7-RXD)") (class "Default")
      (node (ref "R42") (pin "2") (pinfunction "2_2") (pintype "passive"))
      (node (ref "R43") (pin "2") (pinfunction "2_2") (pintype "passive"))
      (node (ref "U7") (pin "20") (pinfunction "RXD_20") (pintype "passive"))
    )
    (net (code "96") (name "Net-(U7-TXD)") (class "Default")
      (node (ref "R39") (pin "2") (pinfunction "2_2") (pintype "passive"))
      (node (ref "R40") (pin "2") (pinfunction "2_2") (pintype "passive"))
      (node (ref "U7") (pin "21") (pinfunction "TXD_21") (pintype "passive"))
    )
    (net (code "97") (name "Net-(U7-VDD)") (class "Default")
      (node (ref "C42") (pin "1") (pinfunction "1_1") (pintype "passive"))
      (node (ref "R25") (pin "1") (pinfunction "1_1") (pintype "passive"))
      (node (ref "U7") (pin "5") (pinfunction "VIO_5") (pintype "passive"))
      (node (ref "U7") (pin "6") (pinfunction "VDD_6") (pintype "passive"))
    )
    (net (code "98") (name "Net-(U7-~{RS}T)") (class "Default")
      (node (ref "R25") (pin "2") (pinfunction "2_2") (pintype "passive"))
      (node (ref "U7") (pin "9") (pinfunction "~{RS}T_9") (pintype "passive"))
    )
    (net (code "99") (name "Net-(U8-Y0)") (class "Default")
      (node (ref "R38") (pin "1") (pinfunction "1_1") (pintype "passive"))
      (node (ref "U8") (pin "24") (pinfunction "Y0_24") (pintype "passive"))
    )
    (net (code "100") (name "Net-(U8-Y1)") (class "Default")
      (node (ref "R41") (pin "1") (pinfunction "1_1") (pintype "passive"))
      (node (ref "U8") (pin "23") (pinfunction "Y1_23") (pintype "passive"))
    )
    (net (code "101") (name "Net-(U11-IN)") (class "Default")
      (node (ref "C54") (pin "2") (pinfunction "2_2") (pintype "passive"))
      (node (ref "U11") (pin "3") (pinfunction "IN_3") (pintype "passive"))
    )
    (net (code "102") (name "Net-(U11-VDD)") (class "Default")
      (node (ref "C47") (pin "1") (pinfunction "1_1") (pintype "passive"))
      (node (ref "R46") (pin "2") (pinfunction "2_2") (pintype "passive"))
      (node (ref "U11") (pin "4") (pinfunction "~{SD}_4") (pintype "passive"))
      (node (ref "U11") (pin "5") (pinfunction "VDD_5") (pintype "passive"))
    )
    (net (code "103") (name "VCC3V3") (class "Default")
      (node (ref "C28") (pin "1") (pinfunction "1_1") (pintype "passive"))
      (node (ref "C29") (pin "2") (pinfunction "2_2") (pintype "passive"))
      (node (ref "C41") (pin "1") (pinfunction "1_1") (pintype "passive"))
      (node (ref "C51") (pin "2") (pinfunction "2_2") (pintype "passive"))
      (node (ref "C52") (pin "1") (pinfunction "1_1") (pintype "passive"))
      (node (ref "C59") (pin "1") (pinfunction "1_1") (pintype "passive"))
      (node (ref "C60") (pin "2") (pinfunction "2_2") (pintype "passive"))
      (node (ref "DS1") (pin "A") (pinfunction "1_A") (pintype "passive"))
      (node (ref "J1") (pin "4") (pinfunction "VDD_4") (pintype "power_in"))
      (node (ref "L1") (pin "2") (pinfunction "2_2") (pintype "passive"))
      (node (ref "P1") (pin "31") (pinfunction "DISP_31") (pintype "passive"))
      (node (ref "P1") (pin "4") (pinfunction "VDD_4") (pintype "passive"))
      (node (ref "P2") (pin "6") (pinfunction "6_6") (pintype "passive"))
      (node (ref "P4") (pin "2") (pinfunction "2_2") (pintype "passive"))
      (node (ref "R16") (pin "1") (pinfunction "1_1") (pintype "passive"))
      (node (ref "R17") (pin "1") (pinfunction "1_1") (pintype "passive"))
      (node (ref "R18") (pin "1") (pinfunction "1_1") (pintype "passive"))
      (node (ref "R19") (pin "1") (pinfunction "1_1") (pintype "passive"))
      (node (ref "R20") (pin "1") (pinfunction "1_1") (pintype "passive"))
      (node (ref "R21") (pin "2") (pinfunction "2_2") (pintype "passive"))
      (node (ref "R22") (pin "2") (pinfunction "2_2") (pintype "passive"))
      (node (ref "R31") (pin "1") (pinfunction "1_1") (pintype "passive"))
      (node (ref "R33") (pin "2") (pinfunction "2_2") (pintype "passive"))
      (node (ref "R36") (pin "1") (pinfunction "1_1") (pintype "passive"))
      (node (ref "R41") (pin "2") (pinfunction "2_2") (pintype "passive"))
      (node (ref "R8") (pin "1") (pinfunction "1_1") (pintype "passive"))
      (node (ref "U10") (pin "3") (pinfunction "IN_3") (pintype "passive"))
      (node (ref "U2") (pin "3") (pinfunction "IN_3") (pintype "passive"))
      (node (ref "U6") (pin "1") (pinfunction "VCC_1") (pintype "passive"))
      (node (ref "U9") (pin "3") (pinfunction "IN_3") (pintype "passive"))
    )
    (net (code "104") (name "VCCIN") (class "Default")
      (node (ref "C23") (pin "1") (pinfunction "1_1") (pintype "passive"))
      (node (ref "C25") (pin "1") (pinfunction "1_1") (pintype "passive"))
      (node (ref "C26") (pin "1") (pinfunction "1_1") (pintype "passive"))
      (node (ref "C27") (pin "1") (pinfunction "1_1") (pintype "passive"))
      (node (ref "C43") (pin "2") (pinfunction "2_2") (pintype "passive"))
      (node (ref "C55") (pin "2") (pinfunction "2_2") (pintype "passive"))
      (node (ref "J2") (pin "1") (pinfunction "VBUS_1") (pintype "power_in"))
      (node (ref "J3") (pin "1") (pinfunction "VBUS_1") (pintype "power_in"))
      (node (ref "L4") (pin "1") (pinfunction "1_1") (pintype "passive"))
      (node (ref "P2") (pin "1") (pinfunction "1_1") (pintype "passive"))
      (node (ref "R46") (pin "1") (pinfunction "1_1") (pintype "passive"))
      (node (ref "U4") (pin "10") (pinfunction "VIN1_10") (pintype "passive"))
      (node (ref "U4") (pin "16") (pinfunction "VCC_16") (pintype "passive"))
      (node (ref "U4") (pin "18") (pinfunction "EN3_18") (pintype "passive"))
      (node (ref "U4") (pin "19") (pinfunction "VIN3_19") (pintype "passive"))
      (node (ref "U4") (pin "7") (pinfunction "VIN2_7") (pintype "passive"))
      (node (ref "U4") (pin "8") (pinfunction "EN2_8") (pintype "passive"))
      (node (ref "U4") (pin "9") (pinfunction "EN1_9") (pintype "passive"))
      (node (ref "U5") (pin "6") (pinfunction "IN_6") (pintype "passive"))
      (node (ref "U7") (pin "7") (pinfunction "REGIN_7") (pintype "passive"))
      (node (ref "U7") (pin "8") (pinfunction "VBUS_8") (pintype "power_in"))
    )
    (net (code "105") (name "VCC_CORE") (class "Default")
      (node (ref "C32") (pin "1") (pinfunction "1_1") (pintype "passive"))
      (node (ref "C33") (pin "2") (pinfunction "2_2") (pintype "passive"))
      (node (ref "L2") (pin "2") (pinfunction "2_2") (pintype "passive"))
      (node (ref "R12") (pin "1") (pinfunction "1_1") (pintype "passive"))
      (node (ref "R24") (pin "2") (pinfunction "2_2") (pintype "passive"))
    )
    (net (code "106") (name "VCC_DRAM") (class "Default")
      (node (ref "C30") (pin "1") (pinfunction "1_1") (pintype "passive"))
      (node (ref "C31") (pin "2") (pinfunction "2_2") (pintype "passive"))
      (node (ref "L3") (pin "2") (pinfunction "2_2") (pintype "passive"))
      (node (ref "R10") (pin "1") (pinfunction "1_1") (pintype "passive"))
    )
    (net (code "107") (name "unconnected-(J2-ID-Pad4)") (class "Default")
      (node (ref "J2") (pin "4") (pinfunction "ID_4") (pintype "passive+no_connect"))
    )
    (net (code "108") (name "unconnected-(J3-ID-Pad4)") (class "Default")
      (node (ref "J3") (pin "4") (pinfunction "ID_4") (pintype "passive"))
    )
    (net (code "109") (name "unconnected-(P3-Pad5)") (class "Default")
      (node (ref "P3") (pin "5") (pinfunction "5_5") (pintype "passive+no_connect"))
    )
    (net (code "110") (name "unconnected-(P3-Pad6)") (class "Default")
      (node (ref "P3") (pin "6") (pinfunction "6_6") (pintype "passive+no_connect"))
    )
    (net (code "111") (name "unconnected-(P3-Pad7)") (class "Default")
      (node (ref "P3") (pin "7") (pinfunction "7_7") (pintype "passive+no_connect"))
    )
    (net (code "112") (name "unconnected-(P3-Pad8)") (class "Default")
      (node (ref "P3") (pin "8") (pinfunction "8_8") (pintype "passive+no_connect"))
    )
    (net (code "113") (name "unconnected-(P3-Pad9)") (class "Default")
      (node (ref "P3") (pin "9") (pinfunction "9_9") (pintype "passive+no_connect"))
    )
    (net (code "114") (name "unconnected-(P3-Pad10)") (class "Default")
      (node (ref "P3") (pin "10") (pinfunction "10_10") (pintype "passive+no_connect"))
    )
    (net (code "115") (name "unconnected-(U7-CTS-Pad18)") (class "Default")
      (node (ref "U7") (pin "18") (pinfunction "CTS_18") (pintype "passive+no_connect"))
    )
    (net (code "116") (name "unconnected-(U7-DCD-Pad24)") (class "Default")
      (node (ref "U7") (pin "24") (pinfunction "DCD_24") (pintype "passive+no_connect"))
    )
    (net (code "117") (name "unconnected-(U7-DSR-Pad22)") (class "Default")
      (node (ref "U7") (pin "22") (pinfunction "DSR_22") (pintype "passive+no_connect"))
    )
    (net (code "118") (name "unconnected-(U7-DTR-Pad23)") (class "Default")
      (node (ref "U7") (pin "23") (pinfunction "DTR_23") (pintype "passive+no_connect"))
    )
    (net (code "119") (name "unconnected-(U7-GPIO.0-Pad14)") (class "Default")
      (node (ref "U7") (pin "14") (pinfunction "GPIO.0_14") (pintype "passive+no_connect"))
    )
    (net (code "120") (name "unconnected-(U7-GPIO.1-Pad13)") (class "Default")
      (node (ref "U7") (pin "13") (pinfunction "GPIO.1_13") (pintype "passive+no_connect"))
    )
    (net (code "121") (name "unconnected-(U7-GPIO.2-Pad12)") (class "Default")
      (node (ref "U7") (pin "12") (pinfunction "GPIO.2_12") (pintype "passive+no_connect"))
    )
    (net (code "122") (name "unconnected-(U7-GPIO.3-Pad11)") (class "Default")
      (node (ref "U7") (pin "11") (pinfunction "GPIO.3_11") (pintype "passive+no_connect"))
    )
    (net (code "123") (name "unconnected-(U7-NC-Pad10)") (class "Default")
      (node (ref "U7") (pin "10") (pinfunction "NC_10") (pintype "passive+no_connect"))
    )
    (net (code "124") (name "unconnected-(U7-RI-Pad1)") (class "Default")
      (node (ref "U7") (pin "1") (pinfunction "RI_1") (pintype "passive+no_connect"))
    )
    (net (code "125") (name "unconnected-(U7-RTS-Pad19)") (class "Default")
      (node (ref "U7") (pin "19") (pinfunction "RTS_19") (pintype "passive+no_connect"))
    )
    (net (code "126") (name "unconnected-(U7-SUSPEND-Pad17)") (class "Default")
      (node (ref "U7") (pin "17") (pinfunction "SUSPEND_17") (pintype "passive+no_connect"))
    )
    (net (code "127") (name "unconnected-(U7-VPP-Pad16)") (class "Default")
      (node (ref "U7") (pin "16") (pinfunction "VPP_16") (pintype "passive+no_connect"))
    )
    (net (code "128") (name "unconnected-(U7-~{SUSPEND}-Pad15)") (class "Default")
      (node (ref "U7") (pin "15") (pinfunction "~{SUSPEND}_15") (pintype "passive+no_connect"))
    )
    (net (code "129") (name "unconnected-(U8-STROBE-Pad1)") (class "Default")
      (node (ref "U8") (pin "1") (pinfunction "STROBE_1") (pintype "passive+no_connect"))
    )
  )
)
